# broncho_lung_breakout.net
KiCad netlist of a schematic drawn in EAGLE
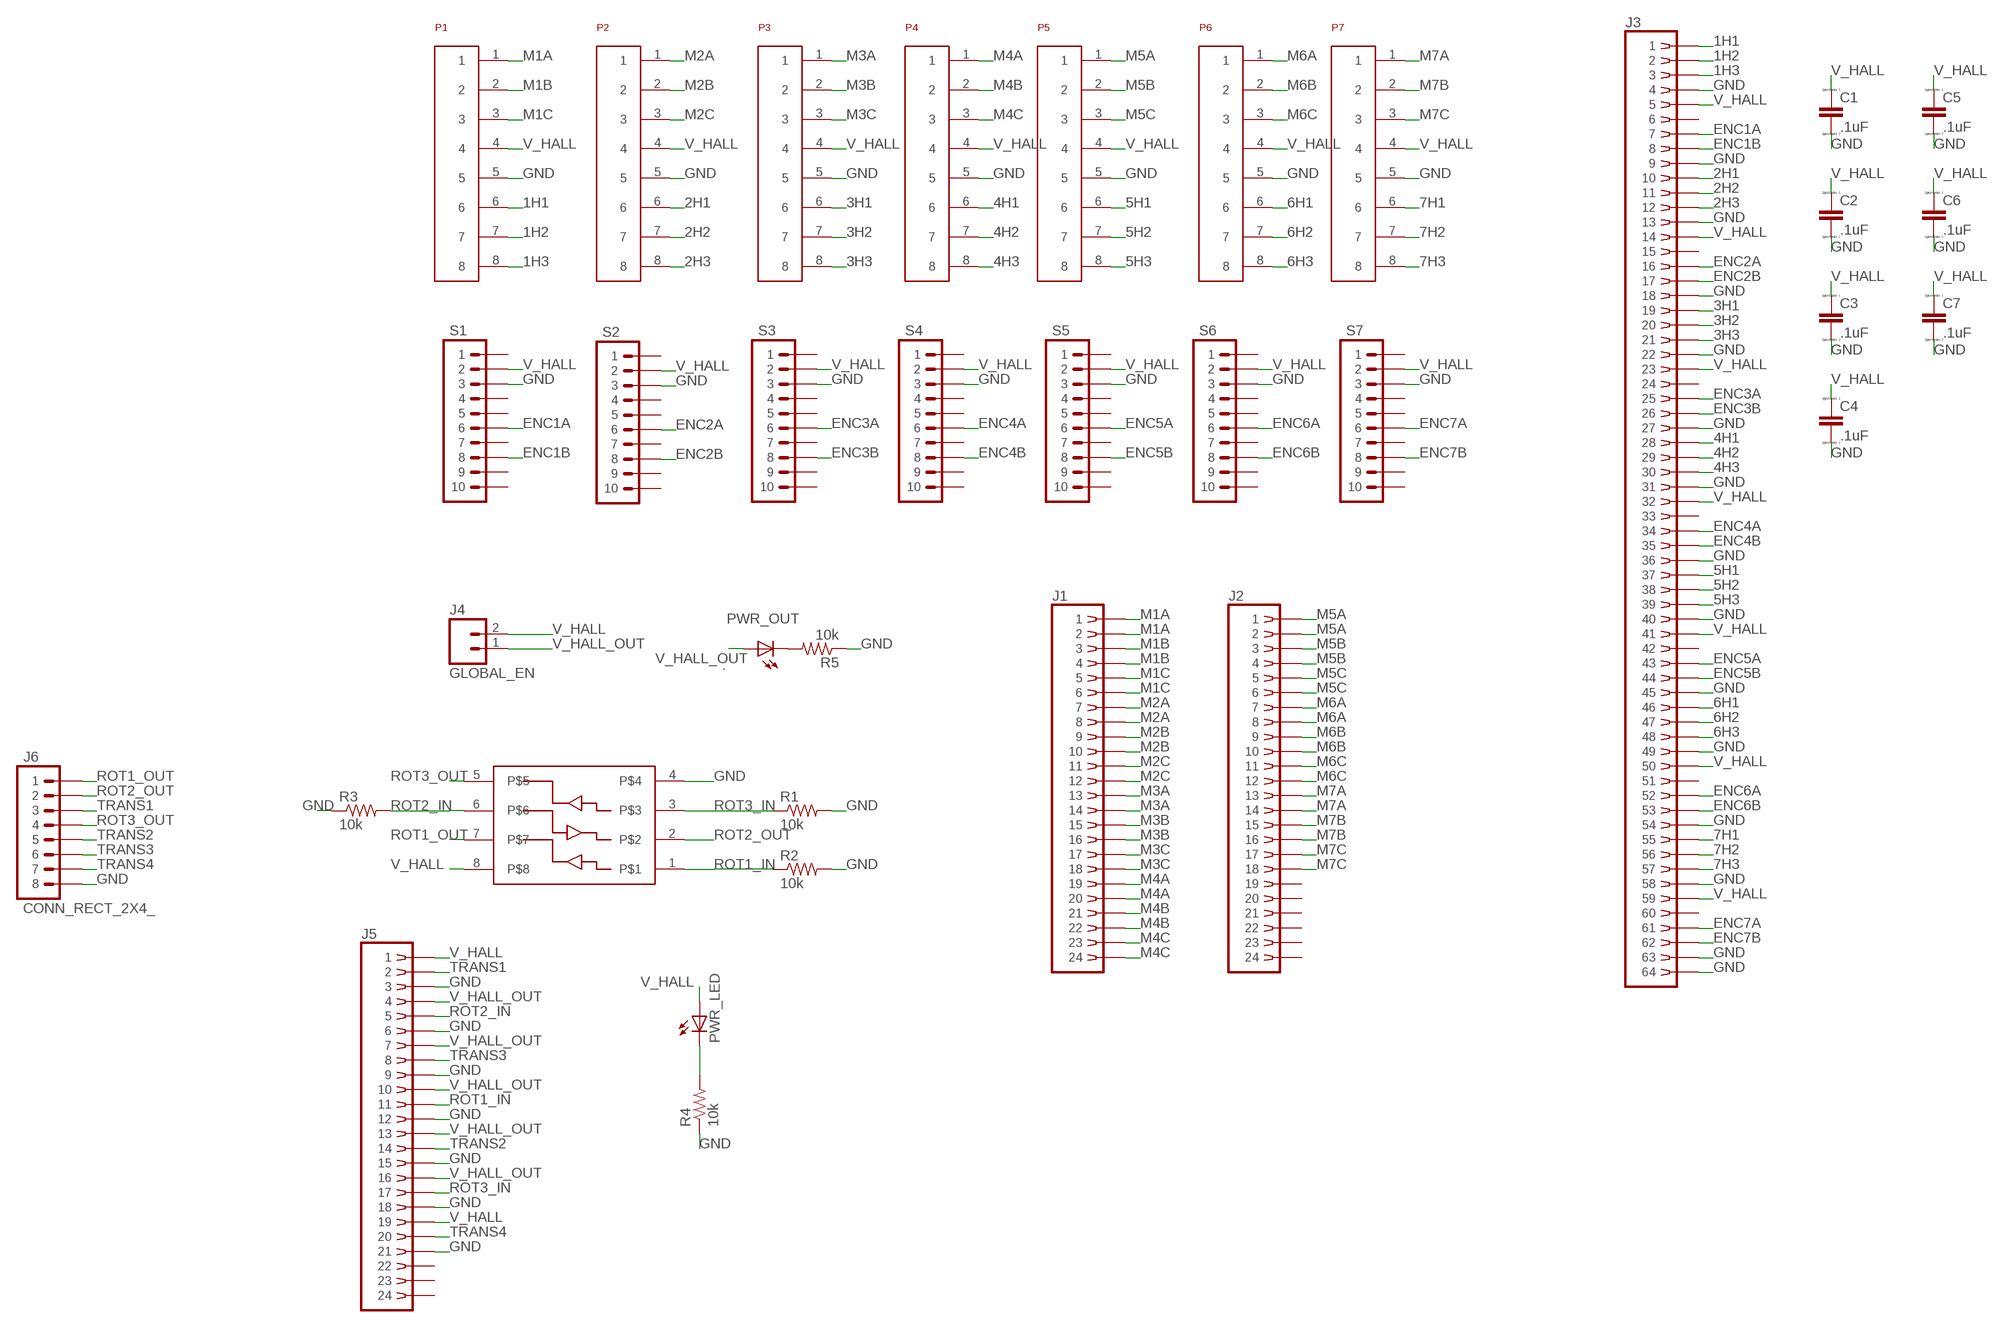
[diagram p0: schematic, sheet 1]

(export (version "E")
  (design (tool "Eeschema 10.0.6"))
  (components
    (comp (ref "C1")
      (value ".1uF")
      (footprint "eagle-import:C0603")
      (libsource (lib "eagle-import") (part "CC0603"))
    )
    (comp (ref "C2")
      (value ".1uF")
      (footprint "eagle-import:C0603")
      (libsource (lib "eagle-import") (part "CC0603"))
    )
    (comp (ref "C3")
      (value ".1uF")
      (footprint "eagle-import:C0603")
      (libsource (lib "eagle-import") (part "CC0603"))
    )
    (comp (ref "C4")
      (value ".1uF")
      (footprint "eagle-import:C0603")
      (libsource (lib "eagle-import") (part "CC0603"))
    )
    (comp (ref "C5")
      (value ".1uF")
      (footprint "eagle-import:C0603")
      (libsource (lib "eagle-import") (part "CC0603"))
    )
    (comp (ref "C6")
      (value ".1uF")
      (footprint "eagle-import:C0603")
      (libsource (lib "eagle-import") (part "CC0603"))
    )
    (comp (ref "C7")
      (value ".1uF")
      (footprint "eagle-import:C0603")
      (libsource (lib "eagle-import") (part "CC0603"))
    )
    (comp (ref "J1")
      (value "CONN_RECT_2X12TH")
      (footprint "eagle-import:CONN_IDC_24_MALE_TH")
      (libsource (lib "eagle-import") (part "CONN_RECT_2X12TH"))
    )
    (comp (ref "J2")
      (value "CONN_RECT_2X12TH")
      (footprint "eagle-import:CONN_IDC_24_MALE_TH")
      (libsource (lib "eagle-import") (part "CONN_RECT_2X12TH"))
    )
    (comp (ref "J3")
      (value "CONN_RECT_2X32NOHOLES")
      (footprint "eagle-import:CONN_IDC_64_MALE_TH_NOHOLES")
      (libsource (lib "eagle-import") (part "CONN_RECT_2X32NOHOLES"))
    )
    (comp (ref "J4")
      (value "GLOBAL_EN")
      (footprint "eagle-import:6410-02")
      (libsource (lib "eagle-import") (part "22-?-0227-2021"))
    )
    (comp (ref "J5")
      (value "CONN_RECT_2X12TH")
      (footprint "eagle-import:CONN_IDC_24_MALE_TH")
      (libsource (lib "eagle-import") (part "CONN_RECT_2X12TH"))
    )
    (comp (ref "J6")
      (value "CONN_RECT_2X4_")
      (footprint "eagle-import:2X4")
      (libsource (lib "eagle-import") (part "CONN_RECT_2X4_"))
    )
    (comp (ref "P1")
      (value "MKS-1650")
      (footprint "eagle-import:MKS-1650")
      (libsource (lib "eagle-import") (part "MKS-1650"))
    )
    (comp (ref "P2")
      (value "MKS-1650")
      (footprint "eagle-import:MKS-1650")
      (libsource (lib "eagle-import") (part "MKS-1650"))
    )
    (comp (ref "P3")
      (value "MKS-1650")
      (footprint "eagle-import:MKS-1650")
      (libsource (lib "eagle-import") (part "MKS-1650"))
    )
    (comp (ref "P4")
      (value "MKS-1650")
      (footprint "eagle-import:MKS-1650")
      (libsource (lib "eagle-import") (part "MKS-1650"))
    )
    (comp (ref "P5")
      (value "MKS-1650")
      (footprint "eagle-import:MKS-1650")
      (libsource (lib "eagle-import") (part "MKS-1650"))
    )
    (comp (ref "P6")
      (value "MKS-1650")
      (footprint "eagle-import:MKS-1650")
      (libsource (lib "eagle-import") (part "MKS-1650"))
    )
    (comp (ref "P7")
      (value "MKS-1650")
      (footprint "eagle-import:MKS-1650")
      (libsource (lib "eagle-import") (part "MKS-1650"))
    )
    (comp (ref "PWR_LED")
      (value ".")
      (footprint "eagle-import:LED-0805")
      (libsource (lib "eagle-import") (part "LED-0805"))
    )
    (comp (ref "PWR_OUT")
      (value ".")
      (footprint "eagle-import:LED-0805")
      (libsource (lib "eagle-import") (part "LED-0805"))
    )
    (comp (ref "R1")
      (value "10k")
      (footprint "eagle-import:0603-RES")
      (libsource (lib "eagle-import") (part "RESISTOR-0603"))
    )
    (comp (ref "R2")
      (value "10k")
      (footprint "eagle-import:0603-RES")
      (libsource (lib "eagle-import") (part "RESISTOR-0603"))
    )
    (comp (ref "R3")
      (value "10k")
      (footprint "eagle-import:0603-RES")
      (libsource (lib "eagle-import") (part "RESISTOR-0603"))
    )
    (comp (ref "R4")
      (value "10k")
      (footprint "eagle-import:0603-RES")
      (libsource (lib "eagle-import") (part "RESISTOR-0603"))
    )
    (comp (ref "R5")
      (value "10k")
      (footprint "eagle-import:0603-RES")
      (libsource (lib "eagle-import") (part "RESISTOR-0603"))
    )
    (comp (ref "S1")
      (value "CONN_RECT_2X5'_VERT")
      (footprint "eagle-import:2X5")
      (libsource (lib "eagle-import") (part "CONN_RECT_2X5'_VERT"))
    )
    (comp (ref "S2")
      (value "CONN_RECT_2X5'_VERT")
      (footprint "eagle-import:2X5")
      (libsource (lib "eagle-import") (part "CONN_RECT_2X5'_VERT"))
    )
    (comp (ref "S3")
      (value "CONN_RECT_2X5'_VERT")
      (footprint "eagle-import:2X5")
      (libsource (lib "eagle-import") (part "CONN_RECT_2X5'_VERT"))
    )
    (comp (ref "S4")
      (value "CONN_RECT_2X5'_VERT")
      (footprint "eagle-import:2X5")
      (libsource (lib "eagle-import") (part "CONN_RECT_2X5'_VERT"))
    )
    (comp (ref "S5")
      (value "CONN_RECT_2X5'_VERT")
      (footprint "eagle-import:2X5")
      (libsource (lib "eagle-import") (part "CONN_RECT_2X5'_VERT"))
    )
    (comp (ref "S6")
      (value "CONN_RECT_2X5'_VERT")
      (footprint "eagle-import:2X5")
      (libsource (lib "eagle-import") (part "CONN_RECT_2X5'_VERT"))
    )
    (comp (ref "S7")
      (value "CONN_RECT_2X5'_VERT")
      (footprint "eagle-import:2X5")
      (libsource (lib "eagle-import") (part "CONN_RECT_2X5'_VERT"))
    )
    (comp (ref "U1")
      (value "INVERTER_3INP")
      (footprint "eagle-import:SOP65P405X120-8")
      (libsource (lib "eagle-import") (part "INVERTER_3INP"))
    )
  )
  (nets
    (net (code "1") (name "/1H1") (class "Default")
      (node (ref "J3") (pin "P$1") (pinfunction "1_P$1") (pintype "passive"))
      (node (ref "P1") (pin "6") (pinfunction "6_6") (pintype "bidirectional"))
    )
    (net (code "2") (name "/1H2") (class "Default")
      (node (ref "J3") (pin "P$2") (pinfunction "2_P$2") (pintype "passive"))
      (node (ref "P1") (pin "7") (pinfunction "7_7") (pintype "bidirectional"))
    )
    (net (code "3") (name "/1H3") (class "Default")
      (node (ref "J3") (pin "P$3") (pinfunction "3_P$3") (pintype "passive"))
      (node (ref "P1") (pin "8") (pinfunction "8_8") (pintype "bidirectional"))
    )
    (net (code "4") (name "/2H1") (class "Default")
      (node (ref "J3") (pin "P$10") (pinfunction "10_P$10") (pintype "passive"))
      (node (ref "P2") (pin "6") (pinfunction "6_6") (pintype "bidirectional"))
    )
    (net (code "5") (name "/2H2") (class "Default")
      (node (ref "J3") (pin "P$11") (pinfunction "11_P$11") (pintype "passive"))
      (node (ref "P2") (pin "7") (pinfunction "7_7") (pintype "bidirectional"))
    )
    (net (code "6") (name "/2H3") (class "Default")
      (node (ref "J3") (pin "P$12") (pinfunction "12_P$12") (pintype "passive"))
      (node (ref "P2") (pin "8") (pinfunction "8_8") (pintype "bidirectional"))
    )
    (net (code "7") (name "/3H1") (class "Default")
      (node (ref "J3") (pin "P$19") (pinfunction "19_P$19") (pintype "passive"))
      (node (ref "P3") (pin "6") (pinfunction "6_6") (pintype "bidirectional"))
    )
    (net (code "8") (name "/3H2") (class "Default")
      (node (ref "J3") (pin "P$20") (pinfunction "20_P$20") (pintype "passive"))
      (node (ref "P3") (pin "7") (pinfunction "7_7") (pintype "bidirectional"))
    )
    (net (code "9") (name "/3H3") (class "Default")
      (node (ref "J3") (pin "P$21") (pinfunction "21_P$21") (pintype "passive"))
      (node (ref "P3") (pin "8") (pinfunction "8_8") (pintype "bidirectional"))
    )
    (net (code "10") (name "/4H1") (class "Default")
      (node (ref "J3") (pin "P$28") (pinfunction "28_P$28") (pintype "passive"))
      (node (ref "P4") (pin "6") (pinfunction "6_6") (pintype "bidirectional"))
    )
    (net (code "11") (name "/4H2") (class "Default")
      (node (ref "J3") (pin "P$29") (pinfunction "29_P$29") (pintype "passive"))
      (node (ref "P4") (pin "7") (pinfunction "7_7") (pintype "bidirectional"))
    )
    (net (code "12") (name "/4H3") (class "Default")
      (node (ref "J3") (pin "P$30") (pinfunction "30_P$30") (pintype "passive"))
      (node (ref "P4") (pin "8") (pinfunction "8_8") (pintype "bidirectional"))
    )
    (net (code "13") (name "/5H1") (class "Default")
      (node (ref "J3") (pin "P$37") (pinfunction "37_P$37") (pintype "passive"))
      (node (ref "P5") (pin "6") (pinfunction "6_6") (pintype "bidirectional"))
    )
    (net (code "14") (name "/5H2") (class "Default")
      (node (ref "J3") (pin "P$38") (pinfunction "38_P$38") (pintype "passive"))
      (node (ref "P5") (pin "7") (pinfunction "7_7") (pintype "bidirectional"))
    )
    (net (code "15") (name "/5H3") (class "Default")
      (node (ref "J3") (pin "P$39") (pinfunction "39_P$39") (pintype "passive"))
      (node (ref "P5") (pin "8") (pinfunction "8_8") (pintype "bidirectional"))
    )
    (net (code "16") (name "/6H1") (class "Default")
      (node (ref "J3") (pin "P$46") (pinfunction "46_P$46") (pintype "passive"))
      (node (ref "P6") (pin "6") (pinfunction "6_6") (pintype "bidirectional"))
    )
    (net (code "17") (name "/6H2") (class "Default")
      (node (ref "J3") (pin "P$47") (pinfunction "47_P$47") (pintype "passive"))
      (node (ref "P6") (pin "7") (pinfunction "7_7") (pintype "bidirectional"))
    )
    (net (code "18") (name "/6H3") (class "Default")
      (node (ref "J3") (pin "P$48") (pinfunction "48_P$48") (pintype "passive"))
      (node (ref "P6") (pin "8") (pinfunction "8_8") (pintype "bidirectional"))
    )
    (net (code "19") (name "/7H1") (class "Default")
      (node (ref "J3") (pin "P$55") (pinfunction "55_P$55") (pintype "passive"))
      (node (ref "P7") (pin "6") (pinfunction "6_6") (pintype "bidirectional"))
    )
    (net (code "20") (name "/7H2") (class "Default")
      (node (ref "J3") (pin "P$56") (pinfunction "56_P$56") (pintype "passive"))
      (node (ref "P7") (pin "7") (pinfunction "7_7") (pintype "bidirectional"))
    )
    (net (code "21") (name "/7H3") (class "Default")
      (node (ref "J3") (pin "P$57") (pinfunction "57_P$57") (pintype "passive"))
      (node (ref "P7") (pin "8") (pinfunction "8_8") (pintype "bidirectional"))
    )
    (net (code "22") (name "/ENC1A") (class "Default")
      (node (ref "J3") (pin "P$7") (pinfunction "7_P$7") (pintype "passive"))
      (node (ref "S1") (pin "6") (pinfunction "6_6") (pintype "passive"))
    )
    (net (code "23") (name "/ENC1B") (class "Default")
      (node (ref "J3") (pin "P$8") (pinfunction "8_P$8") (pintype "passive"))
      (node (ref "S1") (pin "8") (pinfunction "8_8") (pintype "passive"))
    )
    (net (code "24") (name "/ENC2A") (class "Default")
      (node (ref "J3") (pin "P$16") (pinfunction "16_P$16") (pintype "passive"))
      (node (ref "S2") (pin "6") (pinfunction "6_6") (pintype "passive"))
    )
    (net (code "25") (name "/ENC2B") (class "Default")
      (node (ref "J3") (pin "P$17") (pinfunction "17_P$17") (pintype "passive"))
      (node (ref "S2") (pin "8") (pinfunction "8_8") (pintype "passive"))
    )
    (net (code "26") (name "/ENC3A") (class "Default")
      (node (ref "J3") (pin "P$25") (pinfunction "25_P$25") (pintype "passive"))
      (node (ref "S3") (pin "6") (pinfunction "6_6") (pintype "passive"))
    )
    (net (code "27") (name "/ENC3B") (class "Default")
      (node (ref "J3") (pin "P$26") (pinfunction "26_P$26") (pintype "passive"))
      (node (ref "S3") (pin "8") (pinfunction "8_8") (pintype "passive"))
    )
    (net (code "28") (name "/ENC4A") (class "Default")
      (node (ref "J3") (pin "P$34") (pinfunction "34_P$34") (pintype "passive"))
      (node (ref "S4") (pin "6") (pinfunction "6_6") (pintype "passive"))
    )
    (net (code "29") (name "/ENC4B") (class "Default")
      (node (ref "J3") (pin "P$35") (pinfunction "35_P$35") (pintype "passive"))
      (node (ref "S4") (pin "8") (pinfunction "8_8") (pintype "passive"))
    )
    (net (code "30") (name "/ENC5A") (class "Default")
      (node (ref "J3") (pin "P$43") (pinfunction "43_P$43") (pintype "passive"))
      (node (ref "S5") (pin "6") (pinfunction "6_6") (pintype "passive"))
    )
    (net (code "31") (name "/ENC5B") (class "Default")
      (node (ref "J3") (pin "P$44") (pinfunction "44_P$44") (pintype "passive"))
      (node (ref "S5") (pin "8") (pinfunction "8_8") (pintype "passive"))
    )
    (net (code "32") (name "/ENC6A") (class "Default")
      (node (ref "J3") (pin "P$52") (pinfunction "52_P$52") (pintype "passive"))
      (node (ref "S6") (pin "6") (pinfunction "6_6") (pintype "passive"))
    )
    (net (code "33") (name "/ENC6B") (class "Default")
      (node (ref "J3") (pin "P$53") (pinfunction "53_P$53") (pintype "passive"))
      (node (ref "S6") (pin "8") (pinfunction "8_8") (pintype "passive"))
    )
    (net (code "34") (name "/ENC7A") (class "Default")
      (node (ref "J3") (pin "P$61") (pinfunction "61_P$61") (pintype "passive"))
      (node (ref "S7") (pin "6") (pinfunction "6_6") (pintype "passive"))
    )
    (net (code "35") (name "/ENC7B") (class "Default")
      (node (ref "J3") (pin "P$62") (pinfunction "62_P$62") (pintype "passive"))
      (node (ref "S7") (pin "8") (pinfunction "8_8") (pintype "passive"))
    )
    (net (code "36") (name "/GND") (class "Default")
      (node (ref "C1") (pin "2") (pinfunction "2_2") (pintype "passive"))
      (node (ref "C2") (pin "2") (pinfunction "2_2") (pintype "passive"))
      (node (ref "C3") (pin "2") (pinfunction "2_2") (pintype "passive"))
      (node (ref "C4") (pin "2") (pinfunction "2_2") (pintype "passive"))
      (node (ref "C5") (pin "2") (pinfunction "2_2") (pintype "passive"))
      (node (ref "C6") (pin "2") (pinfunction "2_2") (pintype "passive"))
      (node (ref "C7") (pin "2") (pinfunction "2_2") (pintype "passive"))
      (node (ref "J3") (pin "P$13") (pinfunction "13_P$13") (pintype "passive"))
      (node (ref "J3") (pin "P$18") (pinfunction "18_P$18") (pintype "passive"))
      (node (ref "J3") (pin "P$22") (pinfunction "22_P$22") (pintype "passive"))
      (node (ref "J3") (pin "P$27") (pinfunction "27_P$27") (pintype "passive"))
      (node (ref "J3") (pin "P$31") (pinfunction "31_P$31") (pintype "passive"))
      (node (ref "J3") (pin "P$36") (pinfunction "36_P$36") (pintype "passive"))
      (node (ref "J3") (pin "P$4") (pinfunction "4_P$4") (pintype "passive"))
      (node (ref "J3") (pin "P$40") (pinfunction "40_P$40") (pintype "passive"))
      (node (ref "J3") (pin "P$45") (pinfunction "45_P$45") (pintype "passive"))
      (node (ref "J3") (pin "P$49") (pinfunction "49_P$49") (pintype "passive"))
      (node (ref "J3") (pin "P$54") (pinfunction "54_P$54") (pintype "passive"))
      (node (ref "J3") (pin "P$58") (pinfunction "58_P$58") (pintype "passive"))
      (node (ref "J3") (pin "P$63") (pinfunction "63_P$63") (pintype "passive"))
      (node (ref "J3") (pin "P$64") (pinfunction "64_P$64") (pintype "passive"))
      (node (ref "J3") (pin "P$9") (pinfunction "9_P$9") (pintype "passive"))
      (node (ref "J5") (pin "P$12") (pinfunction "12_P$12") (pintype "passive"))
      (node (ref "J5") (pin "P$15") (pinfunction "15_P$15") (pintype "passive"))
      (node (ref "J5") (pin "P$18") (pinfunction "18_P$18") (pintype "passive"))
      (node (ref "J5") (pin "P$21") (pinfunction "21_P$21") (pintype "passive"))
      (node (ref "J5") (pin "P$3") (pinfunction "3_P$3") (pintype "passive"))
      (node (ref "J5") (pin "P$6") (pinfunction "6_P$6") (pintype "passive"))
      (node (ref "J5") (pin "P$9") (pinfunction "9_P$9") (pintype "passive"))
      (node (ref "J6") (pin "8") (pinfunction "8_8") (pintype "passive"))
      (node (ref "P1") (pin "5") (pinfunction "5_5") (pintype "bidirectional"))
      (node (ref "P2") (pin "5") (pinfunction "5_5") (pintype "bidirectional"))
      (node (ref "P3") (pin "5") (pinfunction "5_5") (pintype "bidirectional"))
      (node (ref "P4") (pin "5") (pinfunction "5_5") (pintype "bidirectional"))
      (node (ref "P5") (pin "5") (pinfunction "5_5") (pintype "bidirectional"))
      (node (ref "P6") (pin "5") (pinfunction "5_5") (pintype "bidirectional"))
      (node (ref "P7") (pin "5") (pinfunction "5_5") (pintype "bidirectional"))
      (node (ref "R1") (pin "2") (pinfunction "2_2") (pintype "passive"))
      (node (ref "R2") (pin "2") (pinfunction "2_2") (pintype "passive"))
      (node (ref "R3") (pin "1") (pinfunction "1_1") (pintype "passive"))
      (node (ref "R4") (pin "1") (pinfunction "1_1") (pintype "passive"))
      (node (ref "R5") (pin "1") (pinfunction "1_1") (pintype "passive"))
      (node (ref "S1") (pin "3") (pinfunction "3_3") (pintype "passive"))
      (node (ref "S2") (pin "3") (pinfunction "3_3") (pintype "passive"))
      (node (ref "S3") (pin "3") (pinfunction "3_3") (pintype "passive"))
      (node (ref "S4") (pin "3") (pinfunction "3_3") (pintype "passive"))
      (node (ref "S5") (pin "3") (pinfunction "3_3") (pintype "passive"))
      (node (ref "S6") (pin "3") (pinfunction "3_3") (pintype "passive"))
      (node (ref "S7") (pin "3") (pinfunction "3_3") (pintype "passive"))
      (node (ref "U1") (pin "4") (pinfunction "P$4_4") (pintype "bidirectional"))
    )
    (net (code "37") (name "/M1A") (class "Default")
      (node (ref "J1") (pin "P$1") (pinfunction "1_P$1") (pintype "passive"))
      (node (ref "J1") (pin "P$2") (pinfunction "2_P$2") (pintype "passive"))
      (node (ref "P1") (pin "1") (pinfunction "1_1") (pintype "bidirectional"))
    )
    (net (code "38") (name "/M1B") (class "Default")
      (node (ref "J1") (pin "P$3") (pinfunction "3_P$3") (pintype "passive"))
      (node (ref "J1") (pin "P$4") (pinfunction "4_P$4") (pintype "passive"))
      (node (ref "P1") (pin "2") (pinfunction "2_2") (pintype "bidirectional"))
    )
    (net (code "39") (name "/M1C") (class "Default")
      (node (ref "J1") (pin "P$5") (pinfunction "5_P$5") (pintype "passive"))
      (node (ref "J1") (pin "P$6") (pinfunction "6_P$6") (pintype "passive"))
      (node (ref "P1") (pin "3") (pinfunction "3_3") (pintype "bidirectional"))
    )
    (net (code "40") (name "/M2A") (class "Default")
      (node (ref "J1") (pin "P$7") (pinfunction "7_P$7") (pintype "passive"))
      (node (ref "J1") (pin "P$8") (pinfunction "8_P$8") (pintype "passive"))
      (node (ref "P2") (pin "1") (pinfunction "1_1") (pintype "bidirectional"))
    )
    (net (code "41") (name "/M2B") (class "Default")
      (node (ref "J1") (pin "P$10") (pinfunction "10_P$10") (pintype "passive"))
      (node (ref "J1") (pin "P$9") (pinfunction "9_P$9") (pintype "passive"))
      (node (ref "P2") (pin "2") (pinfunction "2_2") (pintype "bidirectional"))
    )
    (net (code "42") (name "/M2C") (class "Default")
      (node (ref "J1") (pin "P$11") (pinfunction "11_P$11") (pintype "passive"))
      (node (ref "J1") (pin "P$12") (pinfunction "12_P$12") (pintype "passive"))
      (node (ref "P2") (pin "3") (pinfunction "3_3") (pintype "bidirectional"))
    )
    (net (code "43") (name "/M3A") (class "Default")
      (node (ref "J1") (pin "P$13") (pinfunction "13_P$13") (pintype "passive"))
      (node (ref "J1") (pin "P$14") (pinfunction "14_P$14") (pintype "passive"))
      (node (ref "P3") (pin "1") (pinfunction "1_1") (pintype "bidirectional"))
    )
    (net (code "44") (name "/M3B") (class "Default")
      (node (ref "J1") (pin "P$15") (pinfunction "15_P$15") (pintype "passive"))
      (node (ref "J1") (pin "P$16") (pinfunction "16_P$16") (pintype "passive"))
      (node (ref "P3") (pin "2") (pinfunction "2_2") (pintype "bidirectional"))
    )
    (net (code "45") (name "/M3C") (class "Default")
      (node (ref "J1") (pin "P$17") (pinfunction "17_P$17") (pintype "passive"))
      (node (ref "J1") (pin "P$18") (pinfunction "18_P$18") (pintype "passive"))
      (node (ref "P3") (pin "3") (pinfunction "3_3") (pintype "bidirectional"))
    )
    (net (code "46") (name "/M4A") (class "Default")
      (node (ref "J1") (pin "P$19") (pinfunction "19_P$19") (pintype "passive"))
      (node (ref "J1") (pin "P$20") (pinfunction "20_P$20") (pintype "passive"))
      (node (ref "P4") (pin "1") (pinfunction "1_1") (pintype "bidirectional"))
    )
    (net (code "47") (name "/M4B") (class "Default")
      (node (ref "J1") (pin "P$21") (pinfunction "21_P$21") (pintype "passive"))
      (node (ref "J1") (pin "P$22") (pinfunction "22_P$22") (pintype "passive"))
      (node (ref "P4") (pin "2") (pinfunction "2_2") (pintype "bidirectional"))
    )
    (net (code "48") (name "/M4C") (class "Default")
      (node (ref "J1") (pin "P$23") (pinfunction "23_P$23") (pintype "passive"))
      (node (ref "J1") (pin "P$24") (pinfunction "24_P$24") (pintype "passive"))
      (node (ref "P4") (pin "3") (pinfunction "3_3") (pintype "bidirectional"))
    )
    (net (code "49") (name "/M5A") (class "Default")
      (node (ref "J2") (pin "P$1") (pinfunction "1_P$1") (pintype "passive"))
      (node (ref "J2") (pin "P$2") (pinfunction "2_P$2") (pintype "passive"))
      (node (ref "P5") (pin "1") (pinfunction "1_1") (pintype "bidirectional"))
    )
    (net (code "50") (name "/M5B") (class "Default")
      (node (ref "J2") (pin "P$3") (pinfunction "3_P$3") (pintype "passive"))
      (node (ref "J2") (pin "P$4") (pinfunction "4_P$4") (pintype "passive"))
      (node (ref "P5") (pin "2") (pinfunction "2_2") (pintype "bidirectional"))
    )
    (net (code "51") (name "/M5C") (class "Default")
      (node (ref "J2") (pin "P$5") (pinfunction "5_P$5") (pintype "passive"))
      (node (ref "J2") (pin "P$6") (pinfunction "6_P$6") (pintype "passive"))
      (node (ref "P5") (pin "3") (pinfunction "3_3") (pintype "bidirectional"))
    )
    (net (code "52") (name "/M6A") (class "Default")
      (node (ref "J2") (pin "P$7") (pinfunction "7_P$7") (pintype "passive"))
      (node (ref "J2") (pin "P$8") (pinfunction "8_P$8") (pintype "passive"))
      (node (ref "P6") (pin "1") (pinfunction "1_1") (pintype "bidirectional"))
    )
    (net (code "53") (name "/M6B") (class "Default")
      (node (ref "J2") (pin "P$10") (pinfunction "10_P$10") (pintype "passive"))
      (node (ref "J2") (pin "P$9") (pinfunction "9_P$9") (pintype "passive"))
      (node (ref "P6") (pin "2") (pinfunction "2_2") (pintype "bidirectional"))
    )
    (net (code "54") (name "/M6C") (class "Default")
      (node (ref "J2") (pin "P$11") (pinfunction "11_P$11") (pintype "passive"))
      (node (ref "J2") (pin "P$12") (pinfunction "12_P$12") (pintype "passive"))
      (node (ref "P6") (pin "3") (pinfunction "3_3") (pintype "bidirectional"))
    )
    (net (code "55") (name "/M7A") (class "Default")
      (node (ref "J2") (pin "P$13") (pinfunction "13_P$13") (pintype "passive"))
      (node (ref "J2") (pin "P$14") (pinfunction "14_P$14") (pintype "passive"))
      (node (ref "P7") (pin "1") (pinfunction "1_1") (pintype "bidirectional"))
    )
    (net (code "56") (name "/M7B") (class "Default")
      (node (ref "J2") (pin "P$15") (pinfunction "15_P$15") (pintype "passive"))
      (node (ref "J2") (pin "P$16") (pinfunction "16_P$16") (pintype "passive"))
      (node (ref "P7") (pin "2") (pinfunction "2_2") (pintype "bidirectional"))
    )
    (net (code "57") (name "/M7C") (class "Default")
      (node (ref "J2") (pin "P$17") (pinfunction "17_P$17") (pintype "passive"))
      (node (ref "J2") (pin "P$18") (pinfunction "18_P$18") (pintype "passive"))
      (node (ref "P7") (pin "3") (pinfunction "3_3") (pintype "bidirectional"))
    )
    (net (code "58") (name "/ROT1_IN") (class "Default")
      (node (ref "J5") (pin "P$11") (pinfunction "11_P$11") (pintype "passive"))
      (node (ref "R2") (pin "1") (pinfunction "1_1") (pintype "passive"))
      (node (ref "U1") (pin "1") (pinfunction "P$1_1") (pintype "bidirectional"))
    )
    (net (code "59") (name "/ROT1_OUT") (class "Default")
      (node (ref "J6") (pin "1") (pinfunction "1_1") (pintype "passive"))
      (node (ref "U1") (pin "7") (pinfunction "P$7_7") (pintype "bidirectional"))
    )
    (net (code "60") (name "/ROT2_IN") (class "Default")
      (node (ref "J5") (pin "P$5") (pinfunction "5_P$5") (pintype "passive"))
      (node (ref "R3") (pin "2") (pinfunction "2_2") (pintype "passive"))
      (node (ref "U1") (pin "6") (pinfunction "P$6_6") (pintype "bidirectional"))
    )
    (net (code "61") (name "/ROT2_OUT") (class "Default")
      (node (ref "J6") (pin "2") (pinfunction "2_2") (pintype "passive"))
      (node (ref "U1") (pin "2") (pinfunction "P$2_2") (pintype "bidirectional"))
    )
    (net (code "62") (name "/ROT3_IN") (class "Default")
      (node (ref "J5") (pin "P$17") (pinfunction "17_P$17") (pintype "passive"))
      (node (ref "R1") (pin "1") (pinfunction "1_1") (pintype "passive"))
      (node (ref "U1") (pin "3") (pinfunction "P$3_3") (pintype "bidirectional"))
    )
    (net (code "63") (name "/ROT3_OUT") (class "Default")
      (node (ref "J6") (pin "4") (pinfunction "4_4") (pintype "passive"))
      (node (ref "U1") (pin "5") (pinfunction "P$5_5") (pintype "bidirectional"))
    )
    (net (code "64") (name "/TRANS1") (class "Default")
      (node (ref "J5") (pin "P$2") (pinfunction "2_P$2") (pintype "passive"))
      (node (ref "J6") (pin "3") (pinfunction "3_3") (pintype "passive"))
    )
    (net (code "65") (name "/TRANS2") (class "Default")
      (node (ref "J5") (pin "P$14") (pinfunction "14_P$14") (pintype "passive"))
      (node (ref "J6") (pin "5") (pinfunction "5_5") (pintype "passive"))
    )
    (net (code "66") (name "/TRANS3") (class "Default")
      (node (ref "J5") (pin "P$8") (pinfunction "8_P$8") (pintype "passive"))
      (node (ref "J6") (pin "6") (pinfunction "6_6") (pintype "passive"))
    )
    (net (code "67") (name "/TRANS4") (class "Default")
      (node (ref "J5") (pin "P$20") (pinfunction "20_P$20") (pintype "passive"))
      (node (ref "J6") (pin "7") (pinfunction "7_7") (pintype "passive"))
    )
    (net (code "68") (name "/V_HALL") (class "Default")
      (node (ref "C1") (pin "1") (pinfunction "1_1") (pintype "passive"))
      (node (ref "C2") (pin "1") (pinfunction "1_1") (pintype "passive"))
      (node (ref "C3") (pin "1") (pinfunction "1_1") (pintype "passive"))
      (node (ref "C4") (pin "1") (pinfunction "1_1") (pintype "passive"))
      (node (ref "C5") (pin "1") (pinfunction "1_1") (pintype "passive"))
      (node (ref "C6") (pin "1") (pinfunction "1_1") (pintype "passive"))
      (node (ref "C7") (pin "1") (pinfunction "1_1") (pintype "passive"))
      (node (ref "J3") (pin "P$14") (pinfunction "14_P$14") (pintype "passive"))
      (node (ref "J3") (pin "P$23") (pinfunction "23_P$23") (pintype "passive"))
      (node (ref "J3") (pin "P$32") (pinfunction "32_P$32") (pintype "passive"))
      (node (ref "J3") (pin "P$41") (pinfunction "41_P$41") (pintype "passive"))
      (node (ref "J3") (pin "P$5") (pinfunction "5_P$5") (pintype "passive"))
      (node (ref "J3") (pin "P$50") (pinfunction "50_P$50") (pintype "passive"))
      (node (ref "J3") (pin "P$59") (pinfunction "59_P$59") (pintype "passive"))
      (node (ref "J4") (pin "2") (pinfunction "2_2") (pintype "passive"))
      (node (ref "J5") (pin "P$1") (pinfunction "1_P$1") (pintype "passive"))
      (node (ref "J5") (pin "P$19") (pinfunction "19_P$19") (pintype "passive"))
      (node (ref "P1") (pin "4") (pinfunction "4_4") (pintype "bidirectional"))
      (node (ref "P2") (pin "4") (pinfunction "4_4") (pintype "bidirectional"))
      (node (ref "P3") (pin "4") (pinfunction "4_4") (pintype "bidirectional"))
      (node (ref "P4") (pin "4") (pinfunction "4_4") (pintype "bidirectional"))
      (node (ref "P5") (pin "4") (pinfunction "4_4") (pintype "bidirectional"))
      (node (ref "P6") (pin "4") (pinfunction "4_4") (pintype "bidirectional"))
      (node (ref "P7") (pin "4") (pinfunction "4_4") (pintype "bidirectional"))
      (node (ref "PWR_LED") (pin "A") (pinfunction "A_A") (pintype "passive"))
      (node (ref "S1") (pin "2") (pinfunction "2_2") (pintype "passive"))
      (node (ref "S2") (pin "2") (pinfunction "2_2") (pintype "passive"))
      (node (ref "S3") (pin "2") (pinfunction "2_2") (pintype "passive"))
      (node (ref "S4") (pin "2") (pinfunction "2_2") (pintype "passive"))
      (node (ref "S5") (pin "2") (pinfunction "2_2") (pintype "passive"))
      (node (ref "S6") (pin "2") (pinfunction "2_2") (pintype "passive"))
      (node (ref "S7") (pin "2") (pinfunction "2_2") (pintype "passive"))
      (node (ref "U1") (pin "8") (pinfunction "P$8_8") (pintype "bidirectional"))
    )
    (net (code "69") (name "/V_HALL_OUT") (class "Default")
      (node (ref "J4") (pin "1") (pinfunction "1_1") (pintype "passive"))
      (node (ref "J5") (pin "P$10") (pinfunction "10_P$10") (pintype "passive"))
      (node (ref "J5") (pin "P$13") (pinfunction "13_P$13") (pintype "passive"))
      (node (ref "J5") (pin "P$16") (pinfunction "16_P$16") (pintype "passive"))
      (node (ref "J5") (pin "P$4") (pinfunction "4_P$4") (pintype "passive"))
      (node (ref "J5") (pin "P$7") (pinfunction "7_P$7") (pintype "passive"))
      (node (ref "PWR_OUT") (pin "A") (pinfunction "A_A") (pintype "passive"))
    )
    (net (code "70") (name "Net-(PWR_LED-PadC)") (class "Default")
      (node (ref "PWR_LED") (pin "C") (pinfunction "C_C") (pintype "passive"))
      (node (ref "R4") (pin "2") (pinfunction "2_2") (pintype "passive"))
    )
    (net (code "71") (name "Net-(PWR_OUT-PadC)") (class "Default")
      (node (ref "PWR_OUT") (pin "C") (pinfunction "C_C") (pintype "passive"))
      (node (ref "R5") (pin "2") (pinfunction "2_2") (pintype "passive"))
    )
    (net (code "72") (name "unconnected-(J2-19-PadP$19)") (class "Default")
      (node (ref "J2") (pin "P$19") (pinfunction "19_P$19") (pintype "passive"))
    )
    (net (code "73") (name "unconnected-(J2-20-PadP$20)") (class "Default")
      (node (ref "J2") (pin "P$20") (pinfunction "20_P$20") (pintype "passive"))
    )
    (net (code "74") (name "unconnected-(J2-21-PadP$21)") (class "Default")
      (node (ref "J2") (pin "P$21") (pinfunction "21_P$21") (pintype "passive"))
    )
    (net (code "75") (name "unconnected-(J2-22-PadP$22)") (class "Default")
      (node (ref "J2") (pin "P$22") (pinfunction "22_P$22") (pintype "passive"))
    )
    (net (code "76") (name "unconnected-(J2-23-PadP$23)") (class "Default")
      (node (ref "J2") (pin "P$23") (pinfunction "23_P$23") (pintype "passive"))
    )
    (net (code "77") (name "unconnected-(J2-24-PadP$24)") (class "Default")
      (node (ref "J2") (pin "P$24") (pinfunction "24_P$24") (pintype "passive"))
    )
    (net (code "78") (name "unconnected-(J3-6-PadP$6)") (class "Default")
      (node (ref "J3") (pin "P$6") (pinfunction "6_P$6") (pintype "passive"))
    )
    (net (code "79") (name "unconnected-(J3-15-PadP$15)") (class "Default")
      (node (ref "J3") (pin "P$15") (pinfunction "15_P$15") (pintype "passive"))
    )
    (net (code "80") (name "unconnected-(J3-24-PadP$24)") (class "Default")
      (node (ref "J3") (pin "P$24") (pinfunction "24_P$24") (pintype "passive"))
    )
    (net (code "81") (name "unconnected-(J3-33-PadP$33)") (class "Default")
      (node (ref "J3") (pin "P$33") (pinfunction "33_P$33") (pintype "passive"))
    )
    (net (code "82") (name "unconnected-(J3-42-PadP$42)") (class "Default")
      (node (ref "J3") (pin "P$42") (pinfunction "42_P$42") (pintype "passive"))
    )
    (net (code "83") (name "unconnected-(J3-51-PadP$51)") (class "Default")
      (node (ref "J3") (pin "P$51") (pinfunction "51_P$51") (pintype "passive"))
    )
    (net (code "84") (name "unconnected-(J3-60-PadP$60)") (class "Default")
      (node (ref "J3") (pin "P$60") (pinfunction "60_P$60") (pintype "passive"))
    )
    (net (code "85") (name "unconnected-(J5-22-PadP$22)") (class "Default")
      (node (ref "J5") (pin "P$22") (pinfunction "22_P$22") (pintype "passive"))
    )
    (net (code "86") (name "unconnected-(J5-23-PadP$23)") (class "Default")
      (node (ref "J5") (pin "P$23") (pinfunction "23_P$23") (pintype "passive"))
    )
    (net (code "87") (name "unconnected-(J5-24-PadP$24)") (class "Default")
      (node (ref "J5") (pin "P$24") (pinfunction "24_P$24") (pintype "passive"))
    )
    (net (code "88") (name "unconnected-(S1-Pad1)") (class "Default")
      (node (ref "S1") (pin "1") (pinfunction "1_1") (pintype "passive"))
    )
    (net (code "89") (name "unconnected-(S1-Pad4)") (class "Default")
      (node (ref "S1") (pin "4") (pinfunction "4_4") (pintype "passive"))
    )
    (net (code "90") (name "unconnected-(S1-Pad5)") (class "Default")
      (node (ref "S1") (pin "5") (pinfunction "5_5") (pintype "passive"))
    )
    (net (code "91") (name "unconnected-(S1-Pad7)") (class "Default")
      (node (ref "S1") (pin "7") (pinfunction "7_7") (pintype "passive"))
    )
    (net (code "92") (name "unconnected-(S1-Pad9)") (class "Default")
      (node (ref "S1") (pin "9") (pinfunction "9_9") (pintype "passive"))
    )
    (net (code "93") (name "unconnected-(S1-Pad10)") (class "Default")
      (node (ref "S1") (pin "10") (pinfunction "10_10") (pintype "passive"))
    )
    (net (code "94") (name "unconnected-(S2-Pad1)") (class "Default")
      (node (ref "S2") (pin "1") (pinfunction "1_1") (pintype "passive"))
    )
    (net (code "95") (name "unconnected-(S2-Pad4)") (class "Default")
      (node (ref "S2") (pin "4") (pinfunction "4_4") (pintype "passive"))
    )
    (net (code "96") (name "unconnected-(S2-Pad5)") (class "Default")
      (node (ref "S2") (pin "5") (pinfunction "5_5") (pintype "passive"))
    )
    (net (code "97") (name "unconnected-(S2-Pad7)") (class "Default")
      (node (ref "S2") (pin "7") (pinfunction "7_7") (pintype "passive"))
    )
    (net (code "98") (name "unconnected-(S2-Pad9)") (class "Default")
      (node (ref "S2") (pin "9") (pinfunction "9_9") (pintype "passive"))
    )
    (net (code "99") (name "unconnected-(S2-Pad10)") (class "Default")
      (node (ref "S2") (pin "10") (pinfunction "10_10") (pintype "passive"))
    )
    (net (code "100") (name "unconnected-(S3-Pad1)") (class "Default")
      (node (ref "S3") (pin "1") (pinfunction "1_1") (pintype "passive"))
    )
    (net (code "101") (name "unconnected-(S3-Pad4)") (class "Default")
      (node (ref "S3") (pin "4") (pinfunction "4_4") (pintype "passive"))
    )
    (net (code "102") (name "unconnected-(S3-Pad5)") (class "Default")
      (node (ref "S3") (pin "5") (pinfunction "5_5") (pintype "passive"))
    )
    (net (code "103") (name "unconnected-(S3-Pad7)") (class "Default")
      (node (ref "S3") (pin "7") (pinfunction "7_7") (pintype "passive"))
    )
    (net (code "104") (name "unconnected-(S3-Pad9)") (class "Default")
      (node (ref "S3") (pin "9") (pinfunction "9_9") (pintype "passive"))
    )
    (net (code "105") (name "unconnected-(S3-Pad10)") (class "Default")
      (node (ref "S3") (pin "10") (pinfunction "10_10") (pintype "passive"))
    )
    (net (code "106") (name "unconnected-(S4-Pad1)") (class "Default")
      (node (ref "S4") (pin "1") (pinfunction "1_1") (pintype "passive"))
    )
    (net (code "107") (name "unconnected-(S4-Pad4)") (class "Default")
      (node (ref "S4") (pin "4") (pinfunction "4_4") (pintype "passive"))
    )
    (net (code "108") (name "unconnected-(S4-Pad5)") (class "Default")
      (node (ref "S4") (pin "5") (pinfunction "5_5") (pintype "passive"))
    )
    (net (code "109") (name "unconnected-(S4-Pad7)") (class "Default")
      (node (ref "S4") (pin "7") (pinfunction "7_7") (pintype "passive"))
    )
    (net (code "110") (name "unconnected-(S4-Pad9)") (class "Default")
      (node (ref "S4") (pin "9") (pinfunction "9_9") (pintype "passive"))
    )
    (net (code "111") (name "unconnected-(S4-Pad10)") (class "Default")
      (node (ref "S4") (pin "10") (pinfunction "10_10") (pintype "passive"))
    )
    (net (code "112") (name "unconnected-(S5-Pad1)") (class "Default")
      (node (ref "S5") (pin "1") (pinfunction "1_1") (pintype "passive"))
    )
    (net (code "113") (name "unconnected-(S5-Pad4)") (class "Default")
      (node (ref "S5") (pin "4") (pinfunction "4_4") (pintype "passive"))
    )
    (net (code "114") (name "unconnected-(S5-Pad5)") (class "Default")
      (node (ref "S5") (pin "5") (pinfunction "5_5") (pintype "passive"))
    )
    (net (code "115") (name "unconnected-(S5-Pad7)") (class "Default")
      (node (ref "S5") (pin "7") (pinfunction "7_7") (pintype "passive"))
    )
    (net (code "116") (name "unconnected-(S5-Pad9)") (class "Default")
      (node (ref "S5") (pin "9") (pinfunction "9_9") (pintype "passive"))
    )
    (net (code "117") (name "unconnected-(S5-Pad10)") (class "Default")
      (node (ref "S5") (pin "10") (pinfunction "10_10") (pintype "passive"))
    )
    (net (code "118") (name "unconnected-(S6-Pad1)") (class "Default")
      (node (ref "S6") (pin "1") (pinfunction "1_1") (pintype "passive"))
    )
    (net (code "119") (name "unconnected-(S6-Pad4)") (class "Default")
      (node (ref "S6") (pin "4") (pinfunction "4_4") (pintype "passive"))
    )
    (net (code "120") (name "unconnected-(S6-Pad5)") (class "Default")
      (node (ref "S6") (pin "5") (pinfunction "5_5") (pintype "passive"))
    )
    (net (code "121") (name "unconnected-(S6-Pad7)") (class "Default")
      (node (ref "S6") (pin "7") (pinfunction "7_7") (pintype "passive"))
    )
    (net (code "122") (name "unconnected-(S6-Pad9)") (class "Default")
      (node (ref "S6") (pin "9") (pinfunction "9_9") (pintype "passive"))
    )
    (net (code "123") (name "unconnected-(S6-Pad10)") (class "Default")
      (node (ref "S6") (pin "10") (pinfunction "10_10") (pintype "passive"))
    )
    (net (code "124") (name "unconnected-(S7-Pad1)") (class "Default")
      (node (ref "S7") (pin "1") (pinfunction "1_1") (pintype "passive"))
    )
    (net (code "125") (name "unconnected-(S7-Pad4)") (class "Default")
      (node (ref "S7") (pin "4") (pinfunction "4_4") (pintype "passive"))
    )
    (net (code "126") (name "unconnected-(S7-Pad5)") (class "Default")
      (node (ref "S7") (pin "5") (pinfunction "5_5") (pintype "passive"))
    )
    (net (code "127") (name "unconnected-(S7-Pad7)") (class "Default")
      (node (ref "S7") (pin "7") (pinfunction "7_7") (pintype "passive"))
    )
    (net (code "128") (name "unconnected-(S7-Pad9)") (class "Default")
      (node (ref "S7") (pin "9") (pinfunction "9_9") (pintype "passive"))
    )
    (net (code "129") (name "unconnected-(S7-Pad10)") (class "Default")
      (node (ref "S7") (pin "10") (pinfunction "10_10") (pintype "passive"))
    )
  )
)
